# VR_Interfaces.net
KiCad netlist of a schematic drawn in Altium Designer
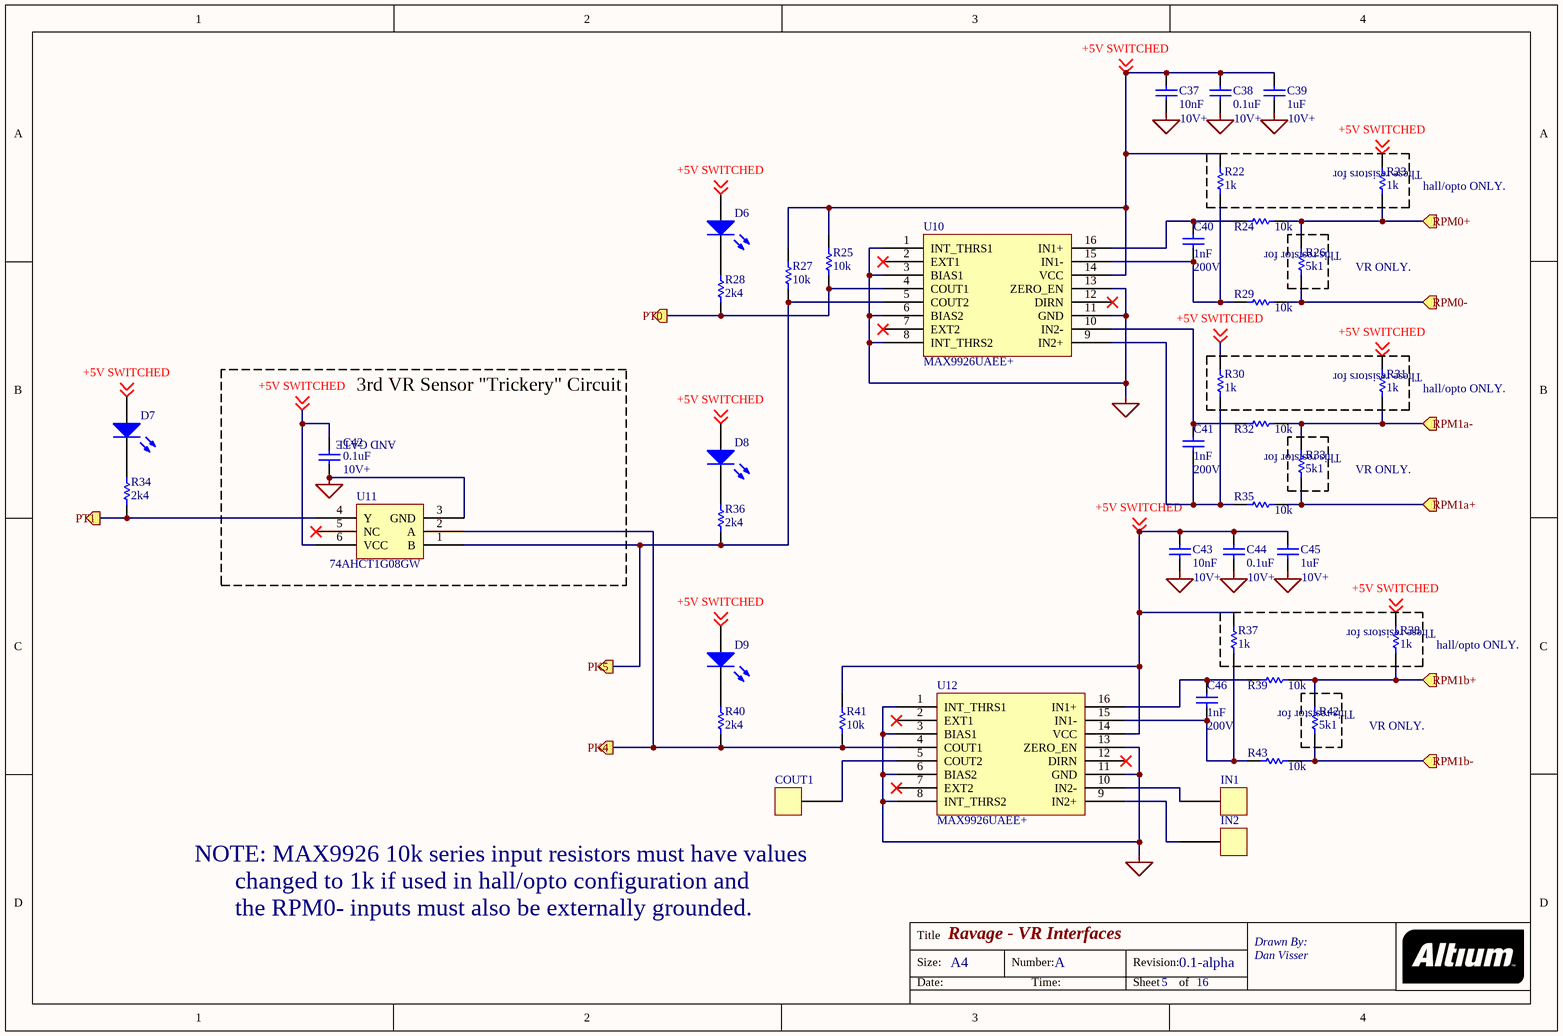
[diagram p0: VR Interfaces.SchDoc]

(export (version "E")
  (design (tool "Eeschema 10.0.6"))
  (components
    (comp (ref "C37")
      (value "10nF")
      (footprint "RAD-0.3")
      (description "Capacitor")
      (fields (field (name "PUBLISHER") "Altium Limited"))
      (libsource (lib "Miscellaneous Devices") (part "Cap"))
    )
    (comp (ref "C38")
      (value "0.1uF")
      (footprint "RAD-0.3")
      (description "Capacitor")
      (fields (field (name "PUBLISHER") "Altium Limited"))
      (libsource (lib "Miscellaneous Devices") (part "Cap"))
    )
    (comp (ref "C39")
      (value "1uF")
      (footprint "RAD-0.3")
      (description "Capacitor")
      (fields (field (name "PUBLISHER") "Altium Limited"))
      (libsource (lib "Miscellaneous Devices") (part "Cap"))
    )
    (comp (ref "C40")
      (value "1nF")
      (footprint "RAD-0.3")
      (description "Capacitor")
      (fields (field (name "PUBLISHER") "Altium Limited"))
      (libsource (lib "Miscellaneous Devices") (part "Cap"))
    )
    (comp (ref "C41")
      (value "1nF")
      (footprint "RAD-0.3")
      (description "Capacitor")
      (fields (field (name "PUBLISHER") "Altium Limited"))
      (libsource (lib "Miscellaneous Devices") (part "Cap"))
    )
    (comp (ref "C42")
      (value "0.1uF")
      (footprint "RAD-0.3")
      (description "Capacitor")
      (fields (field (name "PUBLISHER") "Altium Limited"))
      (libsource (lib "Miscellaneous Devices") (part "Cap"))
    )
    (comp (ref "C43")
      (value "10nF")
      (footprint "RAD-0.3")
      (description "Capacitor")
      (fields (field (name "PUBLISHER") "Altium Limited"))
      (libsource (lib "Miscellaneous Devices") (part "Cap"))
    )
    (comp (ref "C44")
      (value "0.1uF")
      (footprint "RAD-0.3")
      (description "Capacitor")
      (fields (field (name "PUBLISHER") "Altium Limited"))
      (libsource (lib "Miscellaneous Devices") (part "Cap"))
    )
    (comp (ref "C45")
      (value "1uF")
      (footprint "RAD-0.3")
      (description "Capacitor")
      (fields (field (name "PUBLISHER") "Altium Limited"))
      (libsource (lib "Miscellaneous Devices") (part "Cap"))
    )
    (comp (ref "C46")
      (value "1nF")
      (footprint "RAD-0.3")
      (description "Capacitor")
      (fields (field (name "PUBLISHER") "Altium Limited"))
      (libsource (lib "Miscellaneous Devices") (part "Cap"))
    )
    (comp (ref "COUT1") (value "~") (libsource (lib "") (part "HEADER 1_1")))
    (comp (ref "D6")
      (value "~")
      (footprint "LED-0")
      (description "Typical INFRARED GaAs LED")
      (fields (field (name "PUBLISHER") "Altium Limited"))
      (libsource (lib "Miscellaneous Devices") (part "LED0"))
    )
    (comp (ref "D7")
      (value "~")
      (footprint "LED-0")
      (description "Typical INFRARED GaAs LED")
      (fields (field (name "PUBLISHER") "Altium Limited"))
      (libsource (lib "Miscellaneous Devices") (part "LED0"))
    )
    (comp (ref "D8")
      (value "~")
      (footprint "LED-0")
      (description "Typical INFRARED GaAs LED")
      (fields (field (name "PUBLISHER") "Altium Limited"))
      (libsource (lib "Miscellaneous Devices") (part "LED0"))
    )
    (comp (ref "D9")
      (value "~")
      (footprint "LED-0")
      (description "Typical INFRARED GaAs LED")
      (fields (field (name "PUBLISHER") "Altium Limited"))
      (libsource (lib "Miscellaneous Devices") (part "LED0"))
    )
    (comp (ref "IN1") (value "~") (libsource (lib "FreeEMS Schematic Library") (part "HEADER 1")))
    (comp (ref "IN2") (value "~") (libsource (lib "FreeEMS Schematic Library") (part "HEADER 1")))
    (comp (ref "R22")
      (value "1k")
      (footprint "AXIAL-0.3")
      (description "Resistor")
      (fields (field (name "PUBLISHER") "Altium Limited"))
      (libsource (lib "Miscellaneous Devices") (part "Res1"))
    )
    (comp (ref "R23")
      (value "1k")
      (footprint "AXIAL-0.3")
      (description "Resistor")
      (fields (field (name "PUBLISHER") "Altium Limited"))
      (libsource (lib "Miscellaneous Devices") (part "Res1"))
    )
    (comp (ref "R24")
      (value "10k")
      (footprint "AXIAL-0.3")
      (description "Resistor")
      (fields (field (name "PUBLISHER") "Altium Limited"))
      (libsource (lib "Miscellaneous Devices") (part "Res1"))
    )
    (comp (ref "R25")
      (value "10k")
      (footprint "AXIAL-0.3")
      (description "Resistor")
      (fields (field (name "PUBLISHER") "Altium Limited"))
      (libsource (lib "Miscellaneous Devices") (part "Res1"))
    )
    (comp (ref "R26")
      (value "5k1")
      (footprint "AXIAL-0.3")
      (description "Resistor")
      (fields (field (name "PUBLISHER") "Altium Limited"))
      (libsource (lib "Miscellaneous Devices") (part "Res1"))
    )
    (comp (ref "R27")
      (value "10k")
      (footprint "AXIAL-0.3")
      (description "Resistor")
      (fields (field (name "PUBLISHER") "Altium Limited"))
      (libsource (lib "Miscellaneous Devices") (part "Res1"))
    )
    (comp (ref "R28")
      (value "2k4")
      (footprint "AXIAL-0.3")
      (description "Resistor")
      (fields (field (name "PUBLISHER") "Altium Limited"))
      (libsource (lib "Miscellaneous Devices") (part "Res1"))
    )
    (comp (ref "R29")
      (value "10k")
      (footprint "AXIAL-0.3")
      (description "Resistor")
      (fields (field (name "PUBLISHER") "Altium Limited"))
      (libsource (lib "Miscellaneous Devices") (part "Res1"))
    )
    (comp (ref "R30")
      (value "1k")
      (footprint "AXIAL-0.3")
      (description "Resistor")
      (fields (field (name "PUBLISHER") "Altium Limited"))
      (libsource (lib "Miscellaneous Devices") (part "Res1"))
    )
    (comp (ref "R31")
      (value "1k")
      (footprint "AXIAL-0.3")
      (description "Resistor")
      (fields (field (name "PUBLISHER") "Altium Limited"))
      (libsource (lib "Miscellaneous Devices") (part "Res1"))
    )
    (comp (ref "R32")
      (value "10k")
      (footprint "AXIAL-0.3")
      (description "Resistor")
      (fields (field (name "PUBLISHER") "Altium Limited"))
      (libsource (lib "Miscellaneous Devices") (part "Res1"))
    )
    (comp (ref "R33")
      (value "5k1")
      (footprint "AXIAL-0.3")
      (description "Resistor")
      (fields (field (name "PUBLISHER") "Altium Limited"))
      (libsource (lib "Miscellaneous Devices") (part "Res1"))
    )
    (comp (ref "R34")
      (value "2k4")
      (footprint "AXIAL-0.3")
      (description "Resistor")
      (fields (field (name "PUBLISHER") "Altium Limited"))
      (libsource (lib "Miscellaneous Devices") (part "Res1"))
    )
    (comp (ref "R35")
      (value "10k")
      (footprint "AXIAL-0.3")
      (description "Resistor")
      (fields (field (name "PUBLISHER") "Altium Limited"))
      (libsource (lib "Miscellaneous Devices") (part "Res1"))
    )
    (comp (ref "R36")
      (value "2k4")
      (footprint "AXIAL-0.3")
      (description "Resistor")
      (fields (field (name "PUBLISHER") "Altium Limited"))
      (libsource (lib "Miscellaneous Devices") (part "Res1"))
    )
    (comp (ref "R37")
      (value "1k")
      (footprint "AXIAL-0.3")
      (description "Resistor")
      (fields (field (name "PUBLISHER") "Altium Limited"))
      (libsource (lib "Miscellaneous Devices") (part "Res1"))
    )
    (comp (ref "R38")
      (value "1k")
      (footprint "AXIAL-0.3")
      (description "Resistor")
      (fields (field (name "PUBLISHER") "Altium Limited"))
      (libsource (lib "Miscellaneous Devices") (part "Res1"))
    )
    (comp (ref "R39")
      (value "10k")
      (footprint "AXIAL-0.3")
      (description "Resistor")
      (fields (field (name "PUBLISHER") "Altium Limited"))
      (libsource (lib "Miscellaneous Devices") (part "Res1"))
    )
    (comp (ref "R40")
      (value "2k4")
      (footprint "AXIAL-0.3")
      (description "Resistor")
      (fields (field (name "PUBLISHER") "Altium Limited"))
      (libsource (lib "Miscellaneous Devices") (part "Res1"))
    )
    (comp (ref "R41")
      (value "10k")
      (footprint "AXIAL-0.3")
      (description "Resistor")
      (fields (field (name "PUBLISHER") "Altium Limited"))
      (libsource (lib "Miscellaneous Devices") (part "Res1"))
    )
    (comp (ref "R42")
      (value "5k1")
      (footprint "AXIAL-0.3")
      (description "Resistor")
      (fields (field (name "PUBLISHER") "Altium Limited"))
      (libsource (lib "Miscellaneous Devices") (part "Res1"))
    )
    (comp (ref "R43")
      (value "10k")
      (footprint "AXIAL-0.3")
      (description "Resistor")
      (fields (field (name "PUBLISHER") "Altium Limited"))
      (libsource (lib "Miscellaneous Devices") (part "Res1"))
    )
    (comp (ref "U10")
      (value "MAX9926UAEE+")
      (libsource (lib "FreeEMS Schematic Library") (part "MAX9926UAEE+"))
    )
    (comp (ref "U11")
      (value "74AHCT1G08GW")
      (libsource (lib "FreeEMS Schematic Library") (part "NC7SZ32P5X"))
    )
    (comp (ref "U12")
      (value "MAX9926UAEE+")
      (libsource (lib "FreeEMS Schematic Library") (part "MAX9926UAEE+"))
    )
  )
  (nets
    (net (code "1") (name "+5V SWITCHED") (class "Default")
      (node (ref "C37") (pin "2") (pinfunction "2_2") (pintype "passive"))
      (node (ref "C38") (pin "2") (pinfunction "2_2") (pintype "passive"))
      (node (ref "C39") (pin "2") (pinfunction "2_2") (pintype "passive"))
      (node (ref "C42") (pin "2") (pinfunction "2_2") (pintype "passive"))
      (node (ref "C43") (pin "2") (pinfunction "2_2") (pintype "passive"))
      (node (ref "C44") (pin "2") (pinfunction "2_2") (pintype "passive"))
      (node (ref "C45") (pin "2") (pinfunction "2_2") (pintype "passive"))
      (node (ref "D6") (pin "1") (pinfunction "A_1") (pintype "passive"))
      (node (ref "D7") (pin "1") (pinfunction "A_1") (pintype "passive"))
      (node (ref "D8") (pin "1") (pinfunction "A_1") (pintype "passive"))
      (node (ref "D9") (pin "1") (pinfunction "A_1") (pintype "passive"))
      (node (ref "R22") (pin "2") (pinfunction "2_2") (pintype "passive"))
      (node (ref "R23") (pin "2") (pinfunction "2_2") (pintype "passive"))
      (node (ref "R25") (pin "2") (pinfunction "2_2") (pintype "passive"))
      (node (ref "R27") (pin "2") (pinfunction "2_2") (pintype "passive"))
      (node (ref "R30") (pin "2") (pinfunction "2_2") (pintype "passive"))
      (node (ref "R31") (pin "2") (pinfunction "2_2") (pintype "passive"))
      (node (ref "R37") (pin "2") (pinfunction "2_2") (pintype "passive"))
      (node (ref "R38") (pin "2") (pinfunction "2_2") (pintype "passive"))
      (node (ref "R41") (pin "2") (pinfunction "2_2") (pintype "passive"))
      (node (ref "U10") (pin "14") (pinfunction "VCC_14") (pintype "passive"))
      (node (ref "U11") (pin "6") (pinfunction "VCC_6") (pintype "passive"))
      (node (ref "U12") (pin "14") (pinfunction "VCC_14") (pintype "passive"))
    )
    (net (code "2") (name "/PK4") (class "Default")
      (node (ref "R40") (pin "1") (pinfunction "1_1") (pintype "passive"))
      (node (ref "R41") (pin "1") (pinfunction "1_1") (pintype "passive"))
      (node (ref "U11") (pin "2") (pinfunction "A_2") (pintype "passive"))
      (node (ref "U12") (pin "4") (pinfunction "COUT1_4") (pintype "passive"))
    )
    (net (code "3") (name "/PK5") (class "Default")
      (node (ref "R27") (pin "1") (pinfunction "1_1") (pintype "passive"))
      (node (ref "R36") (pin "1") (pinfunction "1_1") (pintype "passive"))
      (node (ref "U10") (pin "5") (pinfunction "COUT2_5") (pintype "passive"))
      (node (ref "U11") (pin "1") (pinfunction "B_1") (pintype "passive"))
    )
    (net (code "4") (name "/PT0") (class "Default")
      (node (ref "R25") (pin "1") (pinfunction "1_1") (pintype "passive"))
      (node (ref "R28") (pin "1") (pinfunction "1_1") (pintype "passive"))
      (node (ref "U10") (pin "4") (pinfunction "COUT1_4") (pintype "passive"))
    )
    (net (code "5") (name "/PT1") (class "Default")
      (node (ref "R34") (pin "1") (pinfunction "1_1") (pintype "passive"))
      (node (ref "U11") (pin "4") (pinfunction "Y_4") (pintype "passive"))
    )
    (net (code "6") (name "/RPM0+") (class "Default")
      (node (ref "R23") (pin "1") (pinfunction "1_1") (pintype "passive"))
      (node (ref "R24") (pin "2") (pinfunction "2_2") (pintype "passive"))
      (node (ref "R26") (pin "2") (pinfunction "2_2") (pintype "passive"))
    )
    (net (code "7") (name "/RPM0-") (class "Default")
      (node (ref "R26") (pin "1") (pinfunction "1_1") (pintype "passive"))
      (node (ref "R29") (pin "2") (pinfunction "2_2") (pintype "passive"))
    )
    (net (code "8") (name "/RPM1a+") (class "Default")
      (node (ref "R33") (pin "1") (pinfunction "1_1") (pintype "passive"))
      (node (ref "R35") (pin "2") (pinfunction "2_2") (pintype "passive"))
    )
    (net (code "9") (name "/RPM1a-") (class "Default")
      (node (ref "R31") (pin "1") (pinfunction "1_1") (pintype "passive"))
      (node (ref "R32") (pin "2") (pinfunction "2_2") (pintype "passive"))
      (node (ref "R33") (pin "2") (pinfunction "2_2") (pintype "passive"))
    )
    (net (code "10") (name "/RPM1b+") (class "Default")
      (node (ref "R38") (pin "1") (pinfunction "1_1") (pintype "passive"))
      (node (ref "R39") (pin "2") (pinfunction "2_2") (pintype "passive"))
      (node (ref "R42") (pin "2") (pinfunction "2_2") (pintype "passive"))
    )
    (net (code "11") (name "/RPM1b-") (class "Default")
      (node (ref "R42") (pin "1") (pinfunction "1_1") (pintype "passive"))
      (node (ref "R43") (pin "2") (pinfunction "2_2") (pintype "passive"))
    )
    (net (code "12") (name "<NO NET>") (class "Default")
      (node (ref "C37") (pin "1") (pinfunction "1_1") (pintype "passive"))
      (node (ref "C38") (pin "1") (pinfunction "1_1") (pintype "passive"))
      (node (ref "C39") (pin "1") (pinfunction "1_1") (pintype "passive"))
      (node (ref "C42") (pin "1") (pinfunction "1_1") (pintype "passive"))
      (node (ref "C43") (pin "1") (pinfunction "1_1") (pintype "passive"))
      (node (ref "C44") (pin "1") (pinfunction "1_1") (pintype "passive"))
      (node (ref "C45") (pin "1") (pinfunction "1_1") (pintype "passive"))
      (node (ref "U10") (pin "1") (pinfunction "INT_THRS1_1") (pintype "passive"))
      (node (ref "U10") (pin "11") (pinfunction "GND_11") (pintype "passive"))
      (node (ref "U10") (pin "13") (pinfunction "ZERO_EN_13") (pintype "passive"))
      (node (ref "U10") (pin "3") (pinfunction "BIAS1_3") (pintype "passive"))
      (node (ref "U10") (pin "6") (pinfunction "BIAS2_6") (pintype "passive"))
      (node (ref "U10") (pin "8") (pinfunction "INT_THRS2_8") (pintype "passive"))
      (node (ref "U11") (pin "3") (pinfunction "GND_3") (pintype "passive"))
      (node (ref "U12") (pin "1") (pinfunction "INT_THRS1_1") (pintype "passive"))
      (node (ref "U12") (pin "11") (pinfunction "GND_11") (pintype "passive"))
      (node (ref "U12") (pin "13") (pinfunction "ZERO_EN_13") (pintype "passive"))
      (node (ref "U12") (pin "3") (pinfunction "BIAS1_3") (pintype "passive"))
      (node (ref "U12") (pin "6") (pinfunction "BIAS2_6") (pintype "passive"))
      (node (ref "U12") (pin "8") (pinfunction "INT_THRS2_8") (pintype "passive"))
    )
    (net (code "13") (name "Net-(D6-K)") (class "Default")
      (node (ref "D6") (pin "2") (pinfunction "K_2") (pintype "passive"))
      (node (ref "R28") (pin "2") (pinfunction "2_2") (pintype "passive"))
    )
    (net (code "14") (name "Net-(D7-K)") (class "Default")
      (node (ref "D7") (pin "2") (pinfunction "K_2") (pintype "passive"))
      (node (ref "R34") (pin "2") (pinfunction "2_2") (pintype "passive"))
    )
    (net (code "15") (name "Net-(D8-K)") (class "Default")
      (node (ref "D8") (pin "2") (pinfunction "K_2") (pintype "passive"))
      (node (ref "R36") (pin "2") (pinfunction "2_2") (pintype "passive"))
    )
    (net (code "16") (name "Net-(D9-K)") (class "Default")
      (node (ref "D9") (pin "2") (pinfunction "K_2") (pintype "passive"))
      (node (ref "R40") (pin "2") (pinfunction "2_2") (pintype "passive"))
    )
    (net (code "17") (name "Net-(U10-IN1+)") (class "Default")
      (node (ref "C40") (pin "2") (pinfunction "2_2") (pintype "passive"))
      (node (ref "R24") (pin "1") (pinfunction "1_1") (pintype "passive"))
      (node (ref "U10") (pin "16") (pinfunction "IN1+_16") (pintype "passive"))
    )
    (net (code "18") (name "Net-(U10-IN1-)") (class "Default")
      (node (ref "C40") (pin "1") (pinfunction "1_1") (pintype "passive"))
      (node (ref "R22") (pin "1") (pinfunction "1_1") (pintype "passive"))
      (node (ref "R29") (pin "1") (pinfunction "1_1") (pintype "passive"))
      (node (ref "U10") (pin "15") (pinfunction "IN1-_15") (pintype "passive"))
    )
    (net (code "19") (name "Net-(U10-IN2+)") (class "Default")
      (node (ref "C41") (pin "1") (pinfunction "1_1") (pintype "passive"))
      (node (ref "R30") (pin "1") (pinfunction "1_1") (pintype "passive"))
      (node (ref "R35") (pin "1") (pinfunction "1_1") (pintype "passive"))
      (node (ref "U10") (pin "9") (pinfunction "IN2+_9") (pintype "passive"))
    )
    (net (code "20") (name "Net-(U10-IN2-)") (class "Default")
      (node (ref "C41") (pin "2") (pinfunction "2_2") (pintype "passive"))
      (node (ref "R32") (pin "1") (pinfunction "1_1") (pintype "passive"))
      (node (ref "U10") (pin "10") (pinfunction "IN2-_10") (pintype "passive"))
    )
    (net (code "21") (name "Net-(U12-COUT2)") (class "Default")
      (node (ref "COUT1") (pin "1") (pinfunction "1_1") (pintype "passive"))
      (node (ref "U12") (pin "5") (pinfunction "COUT2_5") (pintype "passive"))
    )
    (net (code "22") (name "Net-(U12-IN1+)") (class "Default")
      (node (ref "C46") (pin "2") (pinfunction "2_2") (pintype "passive"))
      (node (ref "R39") (pin "1") (pinfunction "1_1") (pintype "passive"))
      (node (ref "U12") (pin "16") (pinfunction "IN1+_16") (pintype "passive"))
    )
    (net (code "23") (name "Net-(U12-IN1-)") (class "Default")
      (node (ref "C46") (pin "1") (pinfunction "1_1") (pintype "passive"))
      (node (ref "R37") (pin "1") (pinfunction "1_1") (pintype "passive"))
      (node (ref "R43") (pin "1") (pinfunction "1_1") (pintype "passive"))
      (node (ref "U12") (pin "15") (pinfunction "IN1-_15") (pintype "passive"))
    )
    (net (code "24") (name "Net-(U12-IN2+)") (class "Default")
      (node (ref "IN2") (pin "1") (pinfunction "1_1") (pintype "passive"))
      (node (ref "U12") (pin "9") (pinfunction "IN2+_9") (pintype "passive"))
    )
    (net (code "25") (name "Net-(U12-IN2-)") (class "Default")
      (node (ref "IN1") (pin "1") (pinfunction "1_1") (pintype "passive"))
      (node (ref "U12") (pin "10") (pinfunction "IN2-_10") (pintype "passive"))
    )
    (net (code "26") (name "unconnected-(U10-DIRN-Pad12)") (class "Default")
      (node (ref "U10") (pin "12") (pinfunction "DIRN_12") (pintype "passive+no_connect"))
    )
    (net (code "27") (name "unconnected-(U10-EXT1-Pad2)") (class "Default")
      (node (ref "U10") (pin "2") (pinfunction "EXT1_2") (pintype "passive+no_connect"))
    )
    (net (code "28") (name "unconnected-(U10-EXT2-Pad7)") (class "Default")
      (node (ref "U10") (pin "7") (pinfunction "EXT2_7") (pintype "passive+no_connect"))
    )
    (net (code "29") (name "unconnected-(U11-NC-Pad5)") (class "Default")
      (node (ref "U11") (pin "5") (pinfunction "NC_5") (pintype "passive+no_connect"))
    )
    (net (code "30") (name "unconnected-(U12-DIRN-Pad12)") (class "Default")
      (node (ref "U12") (pin "12") (pinfunction "DIRN_12") (pintype "passive+no_connect"))
    )
    (net (code "31") (name "unconnected-(U12-EXT1-Pad2)") (class "Default")
      (node (ref "U12") (pin "2") (pinfunction "EXT1_2") (pintype "passive+no_connect"))
    )
    (net (code "32") (name "unconnected-(U12-EXT2-Pad7)") (class "Default")
      (node (ref "U12") (pin "7") (pinfunction "EXT2_7") (pintype "passive+no_connect"))
    )
  )
)
